# Audio_SpeakerDriver.net
KiCad netlist of a schematic drawn in Altium Designer
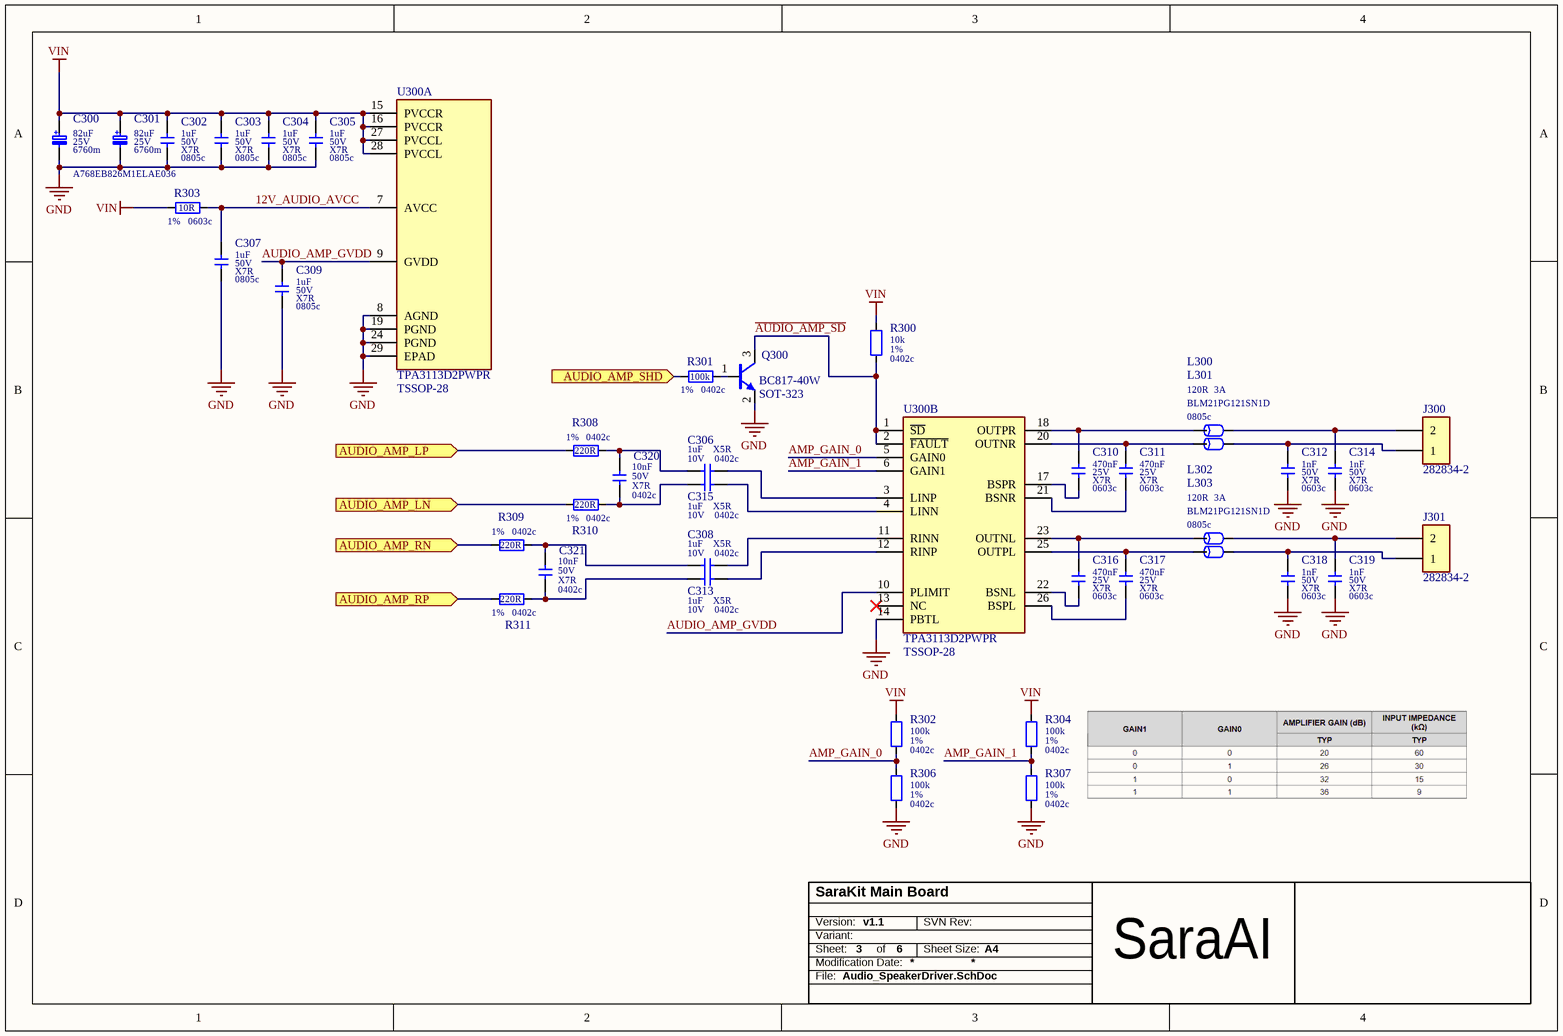
[diagram p0: Audio_SpeakerDriver.SchDoc]

(export (version "E")
  (design (tool "Eeschema 10.0.6"))
  (components
    (comp (ref "C300")
      (value "A768EB826M1ELAE036")
      (footprint "CAPAE660X60L")
      (description "SMT 6760m 82uF 25V 0,2 36mOhm 1.255A 125°")
      (fields
        (field (name "09 PARAMETER 2") "25V")
        (field (name "08 PARAMETER 1") "82uF")
        (field (name "02 MPN") "A768EB826M1ELAE036")
        (field (name "07 PACKAGE") "6760m")
      )
      (libsource (lib "MS_Altium_Lib") (part "CAPACITOR ELECTROLYTIC"))
    )
    (comp (ref "C301")
      (value "A768EB826M1ELAE036")
      (footprint "CAPAE660X60L")
      (description "SMT 6760m 82uF 25V 0,2 36mOhm 1.255A 125°")
      (fields
        (field (name "09 PARAMETER 2") "25V")
        (field (name "08 PARAMETER 1") "82uF")
        (field (name "07 PACKAGE") "6760m")
      )
      (libsource (lib "MS_Altium_Lib") (part "CAPACITOR ELECTROLYTIC"))
    )
    (comp (ref "C302")
      (value "CL21B105KBFNNNG")
      (footprint "CAPC2013X145L")
      (description "SMT 0805c 1uF 50V 10% X7R 6.9MHz 125'C")
      (fields
        (field (name "11 PARAMETER 4") "X7R")
        (field (name "07 PACKAGE") "0805c")
        (field (name "08 PARAMETER 1") "1uF")
        (field (name "09 PARAMETER 2") "50V")
      )
      (libsource (lib "MS_Altium_Lib") (part "CAPACITOR"))
    )
    (comp (ref "C303")
      (value "CL21B105KBFNNNG")
      (footprint "CAPC2013X145L")
      (description "SMT 0805c 1uF 50V 10% X7R 6.9MHz 125'C")
      (fields
        (field (name "11 PARAMETER 4") "X7R")
        (field (name "07 PACKAGE") "0805c")
        (field (name "08 PARAMETER 1") "1uF")
        (field (name "09 PARAMETER 2") "50V")
      )
      (libsource (lib "MS_Altium_Lib") (part "CAPACITOR"))
    )
    (comp (ref "C304")
      (value "CL21B105KBFNNNG")
      (footprint "CAPC2013X145L")
      (description "SMT 0805c 1uF 50V 10% X7R 6.9MHz 125'C")
      (fields
        (field (name "11 PARAMETER 4") "X7R")
        (field (name "07 PACKAGE") "0805c")
        (field (name "08 PARAMETER 1") "1uF")
        (field (name "09 PARAMETER 2") "50V")
      )
      (libsource (lib "MS_Altium_Lib") (part "CAPACITOR"))
    )
    (comp (ref "C305")
      (value "CL21B105KBFNNNG")
      (footprint "CAPC2013X145L")
      (description "SMT 0805c 1uF 50V 10% X7R 6.9MHz 125'C")
      (fields
        (field (name "11 PARAMETER 4") "X7R")
        (field (name "07 PACKAGE") "0805c")
        (field (name "08 PARAMETER 1") "1uF")
        (field (name "09 PARAMETER 2") "50V")
      )
      (libsource (lib "MS_Altium_Lib") (part "CAPACITOR"))
    )
    (comp (ref "C306")
      (value "CL05A105KP5NNNC")
      (footprint "CAPC1005X60L")
      (description "SMT 0402c 1uF 10V 10% X5R 10.2MHz 85'C")
      (fields
        (field (name "11 PARAMETER 4") "X5R")
        (field (name "07 PACKAGE") "0402c")
        (field (name "08 PARAMETER 1") "1uF")
        (field (name "09 PARAMETER 2") "10V")
      )
      (libsource (lib "MS_Altium_Lib") (part "CAPACITOR"))
    )
    (comp (ref "C307")
      (value "CL21B105KBFNNNG")
      (footprint "CAPC2013X145L")
      (description "SMT 0805c 1uF 50V 10% X7R 6.9MHz 125'C")
      (fields
        (field (name "11 PARAMETER 4") "X7R")
        (field (name "07 PACKAGE") "0805c")
        (field (name "08 PARAMETER 1") "1uF")
        (field (name "09 PARAMETER 2") "50V")
      )
      (libsource (lib "MS_Altium_Lib") (part "CAPACITOR"))
    )
    (comp (ref "C308")
      (value "CL05A105KP5NNNC")
      (footprint "CAPC1005X60L")
      (description "SMT 0402c 1uF 10V 10% X5R 10.2MHz 85'C")
      (fields
        (field (name "11 PARAMETER 4") "X5R")
        (field (name "07 PACKAGE") "0402c")
        (field (name "08 PARAMETER 1") "1uF")
        (field (name "09 PARAMETER 2") "10V")
      )
      (libsource (lib "MS_Altium_Lib") (part "CAPACITOR"))
    )
    (comp (ref "C309")
      (value "CL21B105KBFNNNG")
      (footprint "CAPC2013X145L")
      (description "SMT 0805c 1uF 50V 10% X7R 6.9MHz 125'C")
      (fields
        (field (name "11 PARAMETER 4") "X7R")
        (field (name "07 PACKAGE") "0805c")
        (field (name "08 PARAMETER 1") "1uF")
        (field (name "09 PARAMETER 2") "50V")
      )
      (libsource (lib "MS_Altium_Lib") (part "CAPACITOR"))
    )
    (comp (ref "C310")
      (value "CL10B474KA8NNNC")
      (footprint "CAPC1608X90L")
      (description "SMT 0603c 470nF 25V 10% X7R 125°C")
      (fields
        (field (name "11 PARAMETER 4") "X7R")
        (field (name "07 PACKAGE") "0603c")
        (field (name "08 PARAMETER 1") "470nF")
        (field (name "09 PARAMETER 2") "25V")
      )
      (libsource (lib "MS_Altium_Lib") (part "CAPACITOR"))
    )
    (comp (ref "C311")
      (value "CL10B474KA8NNNC")
      (footprint "CAPC1608X90L")
      (description "SMT 0603c 470nF 25V 10% X7R 125°C")
      (fields
        (field (name "11 PARAMETER 4") "X7R")
        (field (name "07 PACKAGE") "0603c")
        (field (name "08 PARAMETER 1") "470nF")
        (field (name "09 PARAMETER 2") "25V")
      )
      (libsource (lib "MS_Altium_Lib") (part "CAPACITOR"))
    )
    (comp (ref "C312")
      (value "CL10B102KB8NNNC")
      (footprint "CAPC1608X90L")
      (description "SMT 0603c 1nF 50V 10% X7R 125°C")
      (fields
        (field (name "11 PARAMETER 4") "X7R")
        (field (name "07 PACKAGE") "0603c")
        (field (name "08 PARAMETER 1") "1nF")
        (field (name "09 PARAMETER 2") "50V")
      )
      (libsource (lib "MS_Altium_Lib") (part "CAPACITOR"))
    )
    (comp (ref "C313")
      (value "CL05A105KP5NNNC")
      (footprint "CAPC1005X60L")
      (description "SMT 0402c 1uF 10V 10% X5R 10.2MHz 85'C")
      (fields
        (field (name "11 PARAMETER 4") "X5R")
        (field (name "07 PACKAGE") "0402c")
        (field (name "08 PARAMETER 1") "1uF")
        (field (name "09 PARAMETER 2") "10V")
      )
      (libsource (lib "MS_Altium_Lib") (part "CAPACITOR"))
    )
    (comp (ref "C314")
      (value "CL10B102KB8NNNC")
      (footprint "CAPC1608X90L")
      (description "SMT 0603c 1nF 50V 10% X7R 125°C")
      (fields
        (field (name "11 PARAMETER 4") "X7R")
        (field (name "07 PACKAGE") "0603c")
        (field (name "08 PARAMETER 1") "1nF")
        (field (name "09 PARAMETER 2") "50V")
      )
      (libsource (lib "MS_Altium_Lib") (part "CAPACITOR"))
    )
    (comp (ref "C315")
      (value "CL05A105KP5NNNC")
      (footprint "CAPC1005X60L")
      (description "SMT 0402c 1uF 10V 10% X5R 10.2MHz 85'C")
      (fields
        (field (name "11 PARAMETER 4") "X5R")
        (field (name "07 PACKAGE") "0402c")
        (field (name "08 PARAMETER 1") "1uF")
        (field (name "09 PARAMETER 2") "10V")
      )
      (libsource (lib "MS_Altium_Lib") (part "CAPACITOR"))
    )
    (comp (ref "C316")
      (value "CL10B474KA8NNNC")
      (footprint "CAPC1608X90L")
      (description "SMT 0603c 470nF 25V 10% X7R 125°C")
      (fields
        (field (name "11 PARAMETER 4") "X7R")
        (field (name "07 PACKAGE") "0603c")
        (field (name "08 PARAMETER 1") "470nF")
        (field (name "09 PARAMETER 2") "25V")
      )
      (libsource (lib "MS_Altium_Lib") (part "CAPACITOR"))
    )
    (comp (ref "C317")
      (value "CL10B474KA8NNNC")
      (footprint "CAPC1608X90L")
      (description "SMT 0603c 470nF 25V 10% X7R 125°C")
      (fields
        (field (name "11 PARAMETER 4") "X7R")
        (field (name "07 PACKAGE") "0603c")
        (field (name "08 PARAMETER 1") "470nF")
        (field (name "09 PARAMETER 2") "25V")
      )
      (libsource (lib "MS_Altium_Lib") (part "CAPACITOR"))
    )
    (comp (ref "C318")
      (value "CL10B102KB8NNNC")
      (footprint "CAPC1608X90L")
      (description "SMT 0603c 1nF 50V 10% X7R 125°C")
      (fields
        (field (name "11 PARAMETER 4") "X7R")
        (field (name "07 PACKAGE") "0603c")
        (field (name "08 PARAMETER 1") "1nF")
        (field (name "09 PARAMETER 2") "50V")
      )
      (libsource (lib "MS_Altium_Lib") (part "CAPACITOR"))
    )
    (comp (ref "C319")
      (value "CL10B102KB8NNNC")
      (footprint "CAPC1608X90L")
      (description "SMT 0603c 1nF 50V 10% X7R 125°C")
      (fields
        (field (name "11 PARAMETER 4") "X7R")
        (field (name "07 PACKAGE") "0603c")
        (field (name "08 PARAMETER 1") "1nF")
        (field (name "09 PARAMETER 2") "50V")
      )
      (libsource (lib "MS_Altium_Lib") (part "CAPACITOR"))
    )
    (comp (ref "C320")
      (value "CL05B103KB5NNN")
      (footprint "CAPC1005X60L")
      (description "SMT 0402c 10nF 50V 0,1 X7R 125°C")
      (fields
        (field (name "11 PARAMETER 4") "X7R")
        (field (name "07 PACKAGE") "0402c")
        (field (name "08 PARAMETER 1") "10nF")
        (field (name "09 PARAMETER 2") "50V")
      )
      (libsource (lib "MS_Altium_Lib") (part "CAPACITOR"))
    )
    (comp (ref "C321")
      (value "CL05B103KB5NNN")
      (footprint "CAPC1005X60L")
      (description "SMT 0402c 10nF 50V 0,1 X7R 125°C")
      (fields
        (field (name "11 PARAMETER 4") "X7R")
        (field (name "07 PACKAGE") "0402c")
        (field (name "08 PARAMETER 1") "10nF")
        (field (name "09 PARAMETER 2") "50V")
      )
      (libsource (lib "MS_Altium_Lib") (part "CAPACITOR"))
    )
    (comp (ref "J300")
      (value "282834-2")
      (footprint "TE 282834-2")
      (description "THT 1x2 2.54mm Straight 150V 10A")
      (fields (field (name "02 MPN") "282834-2"))
      (libsource (lib "MS_Altium_Lib") (part "CONNECTOR 1X2"))
    )
    (comp (ref "J301")
      (value "282834-2")
      (footprint "TE 282834-2")
      (description "THT 1x2 2.54mm Straight 150V 10A")
      (fields (field (name "02 MPN") "282834-2"))
      (libsource (lib "MS_Altium_Lib") (part "CONNECTOR 1X2"))
    )
    (comp (ref "L300")
      (value "BLM21PG121SN1D")
      (footprint "INDC2013X105L")
      (description "SMT 0805c 120R 3A 0.035Ohm 350MHz")
      (fields
        (field (name "09 PARAMETER 2") "3A")
        (field (name "08 PARAMETER 1") "120R")
        (field (name "02 MPN") "BLM21PG121SN1D")
        (field (name "07 PACKAGE") "0805c")
      )
      (libsource (lib "MS_Altium_Lib") (part "BEAD"))
    )
    (comp (ref "L301")
      (value "BLM21PG121SN1D")
      (footprint "INDC2013X105L")
      (description "SMT 0805c 120R 3A 0.035Ohm 350MHz")
      (libsource (lib "MS_Altium_Lib") (part "BEAD"))
    )
    (comp (ref "L302")
      (value "BLM21PG121SN1D")
      (footprint "INDC2013X105L")
      (description "SMT 0805c 120R 3A 0.035Ohm 350MHz")
      (fields
        (field (name "09 PARAMETER 2") "3A")
        (field (name "08 PARAMETER 1") "120R")
        (field (name "02 MPN") "BLM21PG121SN1D")
        (field (name "07 PACKAGE") "0805c")
      )
      (libsource (lib "MS_Altium_Lib") (part "BEAD"))
    )
    (comp (ref "L303")
      (value "BLM21PG121SN1D")
      (footprint "INDC2013X105L")
      (description "SMT 0805c 120R 3A 0.035Ohm 350MHz")
      (libsource (lib "MS_Altium_Lib") (part "BEAD"))
    )
    (comp (ref "Q300")
      (value "BC817-40W")
      (footprint "SOT65P210X110-3L")
      (description "SMT SOT-323 NPN 45V 0.5A 0.2W")
      (fields (field (name "02 MPN") "BC817-40W") (field (name "07 PACKAGE") "SOT-323"))
      (libsource (lib "MS_Altium_Lib") (part "TRANSISTOR NPN 1B 2E 3C"))
    )
    (comp (ref "R300")
      (value "RC0402FR-0710KL")
      (footprint "RESC1005X40L")
      (description "SMT 0402c 10k 1% 62.5mW 100ppm/K 50V")
      (fields
        (field (name "07 PACKAGE") "0402c")
        (field (name "09 PARAMETER 2") "1%")
        (field (name "08 PARAMETER 1") "10k")
      )
      (libsource (lib "") (part "RESISTOR_1"))
    )
    (comp (ref "R301")
      (value "RC0402FR-07100KL")
      (footprint "RESC1005X40L")
      (description "SMT 0402c 100k 1% 62.5mW 100ppm/K 50V")
      (fields
        (field (name "07 PACKAGE") "0402c")
        (field (name "09 PARAMETER 2") "1%")
        (field (name "08 PARAMETER 1") "100k")
      )
      (libsource (lib "MS_Altium_Lib") (part "RESISTOR"))
    )
    (comp (ref "R302")
      (value "RC0402FR-07100KL")
      (footprint "RESC1005X40L")
      (description "SMT 0402c 100k 1% 62.5mW 100ppm/K 50V")
      (fields
        (field (name "07 PACKAGE") "0402c")
        (field (name "09 PARAMETER 2") "1%")
        (field (name "08 PARAMETER 1") "100k")
      )
      (libsource (lib "") (part "RESISTOR_1"))
    )
    (comp (ref "R303")
      (value "RC0603FR-0710RL")
      (footprint "RESC1608X55L")
      (description "SMT 0603c 10R 1% 100mW 100ppm/K 75V")
      (fields
        (field (name "07 PACKAGE") "0603c")
        (field (name "09 PARAMETER 2") "1%")
        (field (name "08 PARAMETER 1") "10R")
      )
      (libsource (lib "MS_Altium_Lib") (part "RESISTOR"))
    )
    (comp (ref "R304")
      (value "RC0402FR-07100KL")
      (footprint "RESC1005X40L")
      (description "SMT 0402c 100k 1% 62.5mW 100ppm/K 50V")
      (fields
        (field (name "07 PACKAGE") "0402c")
        (field (name "09 PARAMETER 2") "1%")
        (field (name "08 PARAMETER 1") "100k")
      )
      (libsource (lib "") (part "RESISTOR_1"))
    )
    (comp (ref "R306")
      (value "RC0402FR-07100KL")
      (footprint "RESC1005X40L")
      (description "SMT 0402c 100k 1% 62.5mW 100ppm/K 50V")
      (fields
        (field (name "07 PACKAGE") "0402c")
        (field (name "09 PARAMETER 2") "1%")
        (field (name "08 PARAMETER 1") "100k")
      )
      (libsource (lib "") (part "RESISTOR_1"))
    )
    (comp (ref "R307")
      (value "RC0402FR-07100KL")
      (footprint "RESC1005X40L")
      (description "SMT 0402c 100k 1% 62.5mW 100ppm/K 50V")
      (fields
        (field (name "07 PACKAGE") "0402c")
        (field (name "09 PARAMETER 2") "1%")
        (field (name "08 PARAMETER 1") "100k")
      )
      (libsource (lib "") (part "RESISTOR_1"))
    )
    (comp (ref "R308")
      (value "RC0402FR-07220RL")
      (footprint "RESC1005X40L")
      (description "SMT 0402c 220R 1% 62.5mW 100ppm/K 50V")
      (fields
        (field (name "07 PACKAGE") "0402c")
        (field (name "09 PARAMETER 2") "1%")
        (field (name "08 PARAMETER 1") "220R")
      )
      (libsource (lib "MS_Altium_Lib") (part "RESISTOR"))
    )
    (comp (ref "R309")
      (value "RC0402FR-07220RL")
      (footprint "RESC1005X40L")
      (description "SMT 0402c 220R 1% 62.5mW 100ppm/K 50V")
      (fields
        (field (name "07 PACKAGE") "0402c")
        (field (name "09 PARAMETER 2") "1%")
        (field (name "08 PARAMETER 1") "220R")
      )
      (libsource (lib "MS_Altium_Lib") (part "RESISTOR"))
    )
    (comp (ref "R310")
      (value "RC0402FR-07220RL")
      (footprint "RESC1005X40L")
      (description "SMT 0402c 220R 1% 62.5mW 100ppm/K 50V")
      (fields
        (field (name "07 PACKAGE") "0402c")
        (field (name "09 PARAMETER 2") "1%")
        (field (name "08 PARAMETER 1") "220R")
      )
      (libsource (lib "MS_Altium_Lib") (part "RESISTOR"))
    )
    (comp (ref "R311")
      (value "RC0402FR-07220RL")
      (footprint "RESC1005X40L")
      (description "SMT 0402c 220R 1% 62.5mW 100ppm/K 50V")
      (fields
        (field (name "07 PACKAGE") "0402c")
        (field (name "09 PARAMETER 2") "1%")
        (field (name "08 PARAMETER 1") "220R")
      )
      (libsource (lib "MS_Altium_Lib") (part "RESISTOR"))
    )
    (comp (ref "U300")
      (value "TPA3113D2PWPR")
      (footprint "TSOP65P640X120_HS-29L")
      (description "SMT TSSOP-28 Speaker 8V - 26V 2x 6W")
      (fields (field (name "02 MPN") "TPA3113D2PWPR") (field (name "07 PACKAGE") "TSSOP-28"))
      (libsource (lib "MS_Altium_Lib") (part "TPA3113D2PWPR"))
    )
  )
  (nets
    (net (code "1") (name "/12V_AUDIO_AVCC") (class "Default")
      (node (ref "C307") (pin "2") (pinfunction "2_2") (pintype "passive"))
      (node (ref "R303") (pin "2") (pinfunction "2_2") (pintype "passive"))
      (node (ref "U300") (pin "7") (pinfunction "AVCC_7") (pintype "passive"))
    )
    (net (code "2") (name "/AMP_GAIN_0") (class "Default")
      (node (ref "R302") (pin "1") (pinfunction "1_1") (pintype "passive"))
      (node (ref "R306") (pin "2") (pinfunction "2_2") (pintype "passive"))
      (node (ref "U300") (pin "5") (pinfunction "GAIN0_5") (pintype "passive"))
    )
    (net (code "3") (name "/AMP_GAIN_1") (class "Default")
      (node (ref "R304") (pin "1") (pinfunction "1_1") (pintype "passive"))
      (node (ref "R307") (pin "2") (pinfunction "2_2") (pintype "passive"))
      (node (ref "U300") (pin "6") (pinfunction "GAIN1_6") (pintype "passive"))
    )
    (net (code "4") (name "/AUDIO_AMP_GVDD") (class "Default")
      (node (ref "C309") (pin "2") (pinfunction "2_2") (pintype "passive"))
      (node (ref "U300") (pin "10") (pinfunction "PLIMIT_10") (pintype "passive"))
      (node (ref "U300") (pin "9") (pinfunction "GVDD_9") (pintype "passive"))
    )
    (net (code "5") (name "/AUDIO_AMP_LN") (class "Default")
      (node (ref "R310") (pin "1") (pinfunction "1_1") (pintype "passive"))
    )
    (net (code "6") (name "/AUDIO_AMP_LP") (class "Default")
      (node (ref "R308") (pin "1") (pinfunction "1_1") (pintype "passive"))
    )
    (net (code "7") (name "/AUDIO_AMP_RN") (class "Default")
      (node (ref "R309") (pin "1") (pinfunction "1_1") (pintype "passive"))
    )
    (net (code "8") (name "/AUDIO_AMP_RP") (class "Default")
      (node (ref "R311") (pin "1") (pinfunction "1_1") (pintype "passive"))
    )
    (net (code "9") (name "/AUDIO_AMP_SD") (class "Default")
      (node (ref "Q300") (pin "3") (pinfunction "C_3") (pintype "passive"))
      (node (ref "R300") (pin "1") (pinfunction "1_1") (pintype "passive"))
      (node (ref "U300") (pin "1") (pinfunction "SD_1") (pintype "passive"))
      (node (ref "U300") (pin "2") (pinfunction "FAULT_2") (pintype "passive"))
    )
    (net (code "10") (name "/AUDIO_AMP_SHD") (class "Default")
      (node (ref "R301") (pin "1") (pinfunction "1_1") (pintype "passive"))
    )
    (net (code "11") (name "GND") (class "Default")
      (node (ref "C300") (pin "2") (pinfunction "2_2") (pintype "passive"))
      (node (ref "C301") (pin "2") (pinfunction "2_2") (pintype "passive"))
      (node (ref "C302") (pin "1") (pinfunction "1_1") (pintype "passive"))
      (node (ref "C303") (pin "1") (pinfunction "1_1") (pintype "passive"))
      (node (ref "C304") (pin "1") (pinfunction "1_1") (pintype "passive"))
      (node (ref "C305") (pin "1") (pinfunction "1_1") (pintype "passive"))
      (node (ref "C307") (pin "1") (pinfunction "1_1") (pintype "passive"))
      (node (ref "C309") (pin "1") (pinfunction "1_1") (pintype "passive"))
      (node (ref "C312") (pin "1") (pinfunction "1_1") (pintype "passive"))
      (node (ref "C314") (pin "1") (pinfunction "1_1") (pintype "passive"))
      (node (ref "C318") (pin "1") (pinfunction "1_1") (pintype "passive"))
      (node (ref "C319") (pin "1") (pinfunction "1_1") (pintype "passive"))
      (node (ref "Q300") (pin "2") (pinfunction "E_2") (pintype "passive"))
      (node (ref "R306") (pin "1") (pinfunction "1_1") (pintype "passive"))
      (node (ref "R307") (pin "1") (pinfunction "1_1") (pintype "passive"))
      (node (ref "U300") (pin "14") (pinfunction "PBTL_14") (pintype "passive"))
      (node (ref "U300") (pin "19") (pinfunction "PGND_19") (pintype "passive"))
      (node (ref "U300") (pin "24") (pinfunction "PGND_24") (pintype "passive"))
      (node (ref "U300") (pin "29") (pinfunction "EPAD_29") (pintype "passive"))
      (node (ref "U300") (pin "8") (pinfunction "AGND_8") (pintype "passive"))
    )
    (net (code "12") (name "Net-(C306-Pad2)") (class "Default")
      (node (ref "C306") (pin "2") (pinfunction "2_2") (pintype "passive"))
      (node (ref "C320") (pin "2") (pinfunction "2_2") (pintype "passive"))
      (node (ref "R308") (pin "2") (pinfunction "2_2") (pintype "passive"))
    )
    (net (code "13") (name "Net-(C308-Pad2)") (class "Default")
      (node (ref "C308") (pin "2") (pinfunction "2_2") (pintype "passive"))
      (node (ref "C321") (pin "2") (pinfunction "2_2") (pintype "passive"))
      (node (ref "R309") (pin "2") (pinfunction "2_2") (pintype "passive"))
    )
    (net (code "14") (name "Net-(C312-Pad2)") (class "Default")
      (node (ref "C312") (pin "2") (pinfunction "2_2") (pintype "passive"))
      (node (ref "J300") (pin "1") (pinfunction "1_1") (pintype "passive"))
      (node (ref "L301") (pin "2") (pinfunction "2_2") (pintype "passive"))
    )
    (net (code "15") (name "Net-(C313-Pad2)") (class "Default")
      (node (ref "C313") (pin "2") (pinfunction "2_2") (pintype "passive"))
      (node (ref "C321") (pin "1") (pinfunction "1_1") (pintype "passive"))
      (node (ref "R311") (pin "2") (pinfunction "2_2") (pintype "passive"))
    )
    (net (code "16") (name "Net-(C314-Pad2)") (class "Default")
      (node (ref "C314") (pin "2") (pinfunction "2_2") (pintype "passive"))
      (node (ref "J300") (pin "2") (pinfunction "2_2") (pintype "passive"))
      (node (ref "L300") (pin "2") (pinfunction "2_2") (pintype "passive"))
    )
    (net (code "17") (name "Net-(C315-Pad2)") (class "Default")
      (node (ref "C315") (pin "2") (pinfunction "2_2") (pintype "passive"))
      (node (ref "C320") (pin "1") (pinfunction "1_1") (pintype "passive"))
      (node (ref "R310") (pin "2") (pinfunction "2_2") (pintype "passive"))
    )
    (net (code "18") (name "Net-(C318-Pad2)") (class "Default")
      (node (ref "C318") (pin "2") (pinfunction "2_2") (pintype "passive"))
      (node (ref "J301") (pin "1") (pinfunction "1_1") (pintype "passive"))
      (node (ref "L303") (pin "2") (pinfunction "2_2") (pintype "passive"))
    )
    (net (code "19") (name "Net-(C319-Pad2)") (class "Default")
      (node (ref "C319") (pin "2") (pinfunction "2_2") (pintype "passive"))
      (node (ref "J301") (pin "2") (pinfunction "2_2") (pintype "passive"))
      (node (ref "L302") (pin "2") (pinfunction "2_2") (pintype "passive"))
    )
    (net (code "20") (name "Net-(Q300-B)") (class "Default")
      (node (ref "Q300") (pin "1") (pinfunction "B_1") (pintype "passive"))
      (node (ref "R301") (pin "2") (pinfunction "2_2") (pintype "passive"))
    )
    (net (code "21") (name "Net-(U300B-BSNL)") (class "Default")
      (node (ref "C316") (pin "1") (pinfunction "1_1") (pintype "passive"))
      (node (ref "U300") (pin "22") (pinfunction "BSNL_22") (pintype "passive"))
    )
    (net (code "22") (name "Net-(U300B-BSNR)") (class "Default")
      (node (ref "C311") (pin "1") (pinfunction "1_1") (pintype "passive"))
      (node (ref "U300") (pin "21") (pinfunction "BSNR_21") (pintype "passive"))
    )
    (net (code "23") (name "Net-(U300B-BSPL)") (class "Default")
      (node (ref "C317") (pin "1") (pinfunction "1_1") (pintype "passive"))
      (node (ref "U300") (pin "26") (pinfunction "BSPL_26") (pintype "passive"))
    )
    (net (code "24") (name "Net-(U300B-BSPR)") (class "Default")
      (node (ref "C310") (pin "1") (pinfunction "1_1") (pintype "passive"))
      (node (ref "U300") (pin "17") (pinfunction "BSPR_17") (pintype "passive"))
    )
    (net (code "25") (name "Net-(U300B-LINN)") (class "Default")
      (node (ref "C315") (pin "1") (pinfunction "1_1") (pintype "passive"))
      (node (ref "U300") (pin "4") (pinfunction "LINN_4") (pintype "passive"))
    )
    (net (code "26") (name "Net-(U300B-LINP)") (class "Default")
      (node (ref "C306") (pin "1") (pinfunction "1_1") (pintype "passive"))
      (node (ref "U300") (pin "3") (pinfunction "LINP_3") (pintype "passive"))
    )
    (net (code "27") (name "Net-(U300B-OUTNL)") (class "Default")
      (node (ref "C316") (pin "2") (pinfunction "2_2") (pintype "passive"))
      (node (ref "L302") (pin "1") (pinfunction "1_1") (pintype "passive"))
      (node (ref "U300") (pin "23") (pinfunction "OUTNL_23") (pintype "passive"))
    )
    (net (code "28") (name "Net-(U300B-OUTNR)") (class "Default")
      (node (ref "C311") (pin "2") (pinfunction "2_2") (pintype "passive"))
      (node (ref "L301") (pin "1") (pinfunction "1_1") (pintype "passive"))
      (node (ref "U300") (pin "20") (pinfunction "OUTNR_20") (pintype "passive"))
    )
    (net (code "29") (name "Net-(U300B-OUTPL)") (class "Default")
      (node (ref "C317") (pin "2") (pinfunction "2_2") (pintype "passive"))
      (node (ref "L303") (pin "1") (pinfunction "1_1") (pintype "passive"))
      (node (ref "U300") (pin "25") (pinfunction "OUTPL_25") (pintype "passive"))
    )
    (net (code "30") (name "Net-(U300B-OUTPR)") (class "Default")
      (node (ref "C310") (pin "2") (pinfunction "2_2") (pintype "passive"))
      (node (ref "L300") (pin "1") (pinfunction "1_1") (pintype "passive"))
      (node (ref "U300") (pin "18") (pinfunction "OUTPR_18") (pintype "passive"))
    )
    (net (code "31") (name "Net-(U300B-RINN)") (class "Default")
      (node (ref "C308") (pin "1") (pinfunction "1_1") (pintype "passive"))
      (node (ref "U300") (pin "11") (pinfunction "RINN_11") (pintype "passive"))
    )
    (net (code "32") (name "Net-(U300B-RINP)") (class "Default")
      (node (ref "C313") (pin "1") (pinfunction "1_1") (pintype "passive"))
      (node (ref "U300") (pin "12") (pinfunction "RINP_12") (pintype "passive"))
    )
    (net (code "33") (name "VIN") (class "Default")
      (node (ref "C300") (pin "1") (pinfunction "1_1") (pintype "passive"))
      (node (ref "C301") (pin "1") (pinfunction "1_1") (pintype "passive"))
      (node (ref "C302") (pin "2") (pinfunction "2_2") (pintype "passive"))
      (node (ref "C303") (pin "2") (pinfunction "2_2") (pintype "passive"))
      (node (ref "C304") (pin "2") (pinfunction "2_2") (pintype "passive"))
      (node (ref "C305") (pin "2") (pinfunction "2_2") (pintype "passive"))
      (node (ref "R300") (pin "2") (pinfunction "2_2") (pintype "passive"))
      (node (ref "R302") (pin "2") (pinfunction "2_2") (pintype "passive"))
      (node (ref "R303") (pin "1") (pinfunction "1_1") (pintype "passive"))
      (node (ref "R304") (pin "2") (pinfunction "2_2") (pintype "passive"))
      (node (ref "U300") (pin "15") (pinfunction "PVCCR_15") (pintype "passive"))
      (node (ref "U300") (pin "16") (pinfunction "PVCCR_16") (pintype "passive"))
      (node (ref "U300") (pin "27") (pinfunction "PVCCL_27") (pintype "passive"))
      (node (ref "U300") (pin "28") (pinfunction "PVCCL_28") (pintype "passive"))
    )
    (net (code "34") (name "unconnected-(U300B-NC-Pad13)") (class "Default")
      (node (ref "U300") (pin "13") (pinfunction "NC_13") (pintype "passive+no_connect"))
    )
  )
)
